# 3xVCO.net
KiCad netlist of a schematic drawn in Altium Designer
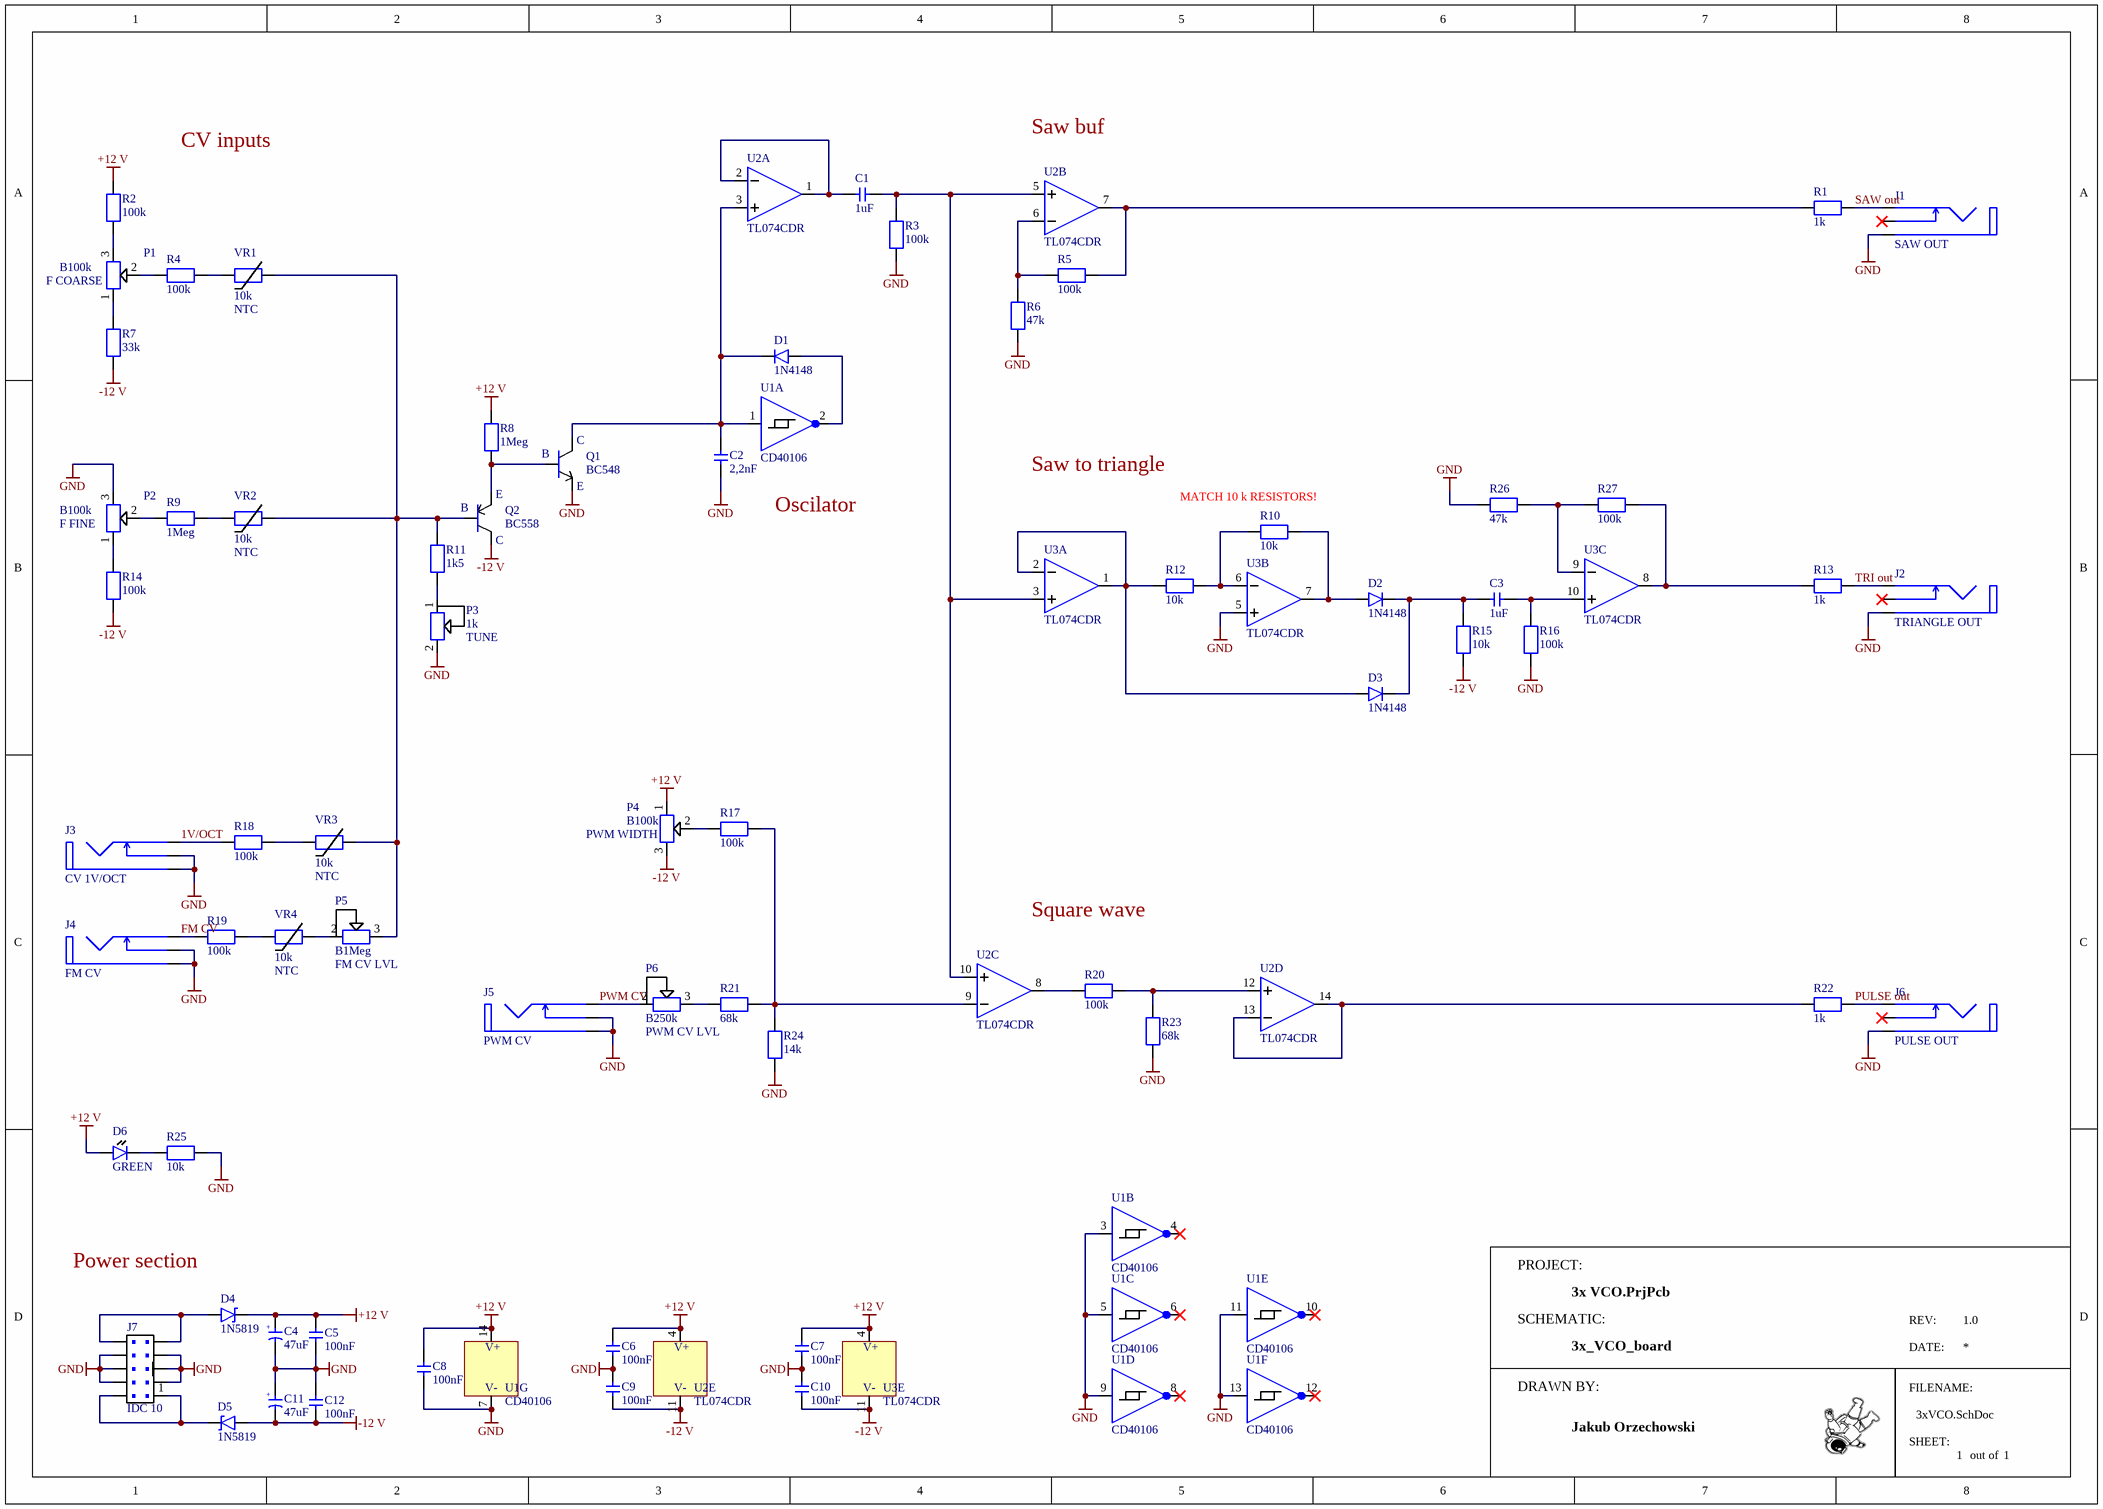
[diagram p0: 3xVCO.SchDoc]

(export (version "E")
  (design (tool "Eeschema 10.0.6"))
  (components
    (comp (ref "C1")
      (value "1uF")
      (footprint "Cap THT 5mm")
      (description "THT Capacitor Non-Polarised 5 mm Pitch")
      (fields (field (name "Comment") "CAP"))
      (libsource (lib "Generic components") (part "Capacitor THT 5mm"))
    )
    (comp (ref "C2")
      (value "2,2nF")
      (footprint "Cap THT 5mm")
      (description "THT Capacitor Non-Polarised 5 mm Pitch")
      (fields (field (name "Comment") "CAP"))
      (libsource (lib "Generic components") (part "Capacitor THT 5mm"))
    )
    (comp (ref "C3")
      (value "1uF")
      (footprint "Cap THT 5mm")
      (description "THT Capacitor Non-Polarised 5 mm Pitch")
      (fields (field (name "Comment") "CAP"))
      (libsource (lib "Generic components") (part "Capacitor THT 5mm"))
    )
    (comp (ref "C4")
      (value "47uF")
      (footprint "Cap electrolytic THT 5mm")
      (description "THT Electrolytic Capacitor 5 mm Diameter")
      (fields (field (name "Comment") "CAP"))
      (libsource (lib "Generic components") (part "Capacitor Electr THT 5mm"))
    )
    (comp (ref "C5")
      (value "100nF")
      (footprint "Cap THT 5mm")
      (description "THT Capacitor Non-Polarised 5 mm Pitch")
      (fields (field (name "Comment") "CAP"))
      (libsource (lib "Generic components") (part "Capacitor THT 5mm"))
    )
    (comp (ref "C6")
      (value "100nF")
      (footprint "Cap THT 5mm")
      (description "THT Capacitor Non-Polarised 5 mm Pitch")
      (fields (field (name "Comment") "CAP"))
      (libsource (lib "Generic components") (part "Capacitor THT 5mm"))
    )
    (comp (ref "C7")
      (value "100nF")
      (footprint "Cap THT 5mm")
      (description "THT Capacitor Non-Polarised 5 mm Pitch")
      (fields (field (name "Comment") "CAP"))
      (libsource (lib "Generic components") (part "Capacitor THT 5mm"))
    )
    (comp (ref "C8")
      (value "100nF")
      (footprint "Cap THT 5mm")
      (description "THT Capacitor Non-Polarised 5 mm Pitch")
      (fields (field (name "Comment") "CAP"))
      (libsource (lib "Generic components") (part "Capacitor THT 5mm"))
    )
    (comp (ref "C9")
      (value "100nF")
      (footprint "Cap THT 5mm")
      (description "THT Capacitor Non-Polarised 5 mm Pitch")
      (fields (field (name "Comment") "CAP"))
      (libsource (lib "Generic components") (part "Capacitor THT 5mm"))
    )
    (comp (ref "C10")
      (value "100nF")
      (footprint "Cap THT 5mm")
      (description "THT Capacitor Non-Polarised 5 mm Pitch")
      (fields (field (name "Comment") "CAP"))
      (libsource (lib "Generic components") (part "Capacitor THT 5mm"))
    )
    (comp (ref "C11")
      (value "47uF")
      (footprint "Cap electrolytic THT 5mm")
      (description "THT Electrolytic Capacitor 5 mm Diameter")
      (fields (field (name "Comment") "CAP"))
      (libsource (lib "Generic components") (part "Capacitor Electr THT 5mm"))
    )
    (comp (ref "C12")
      (value "100nF")
      (footprint "Cap THT 5mm")
      (description "THT Capacitor Non-Polarised 5 mm Pitch")
      (fields (field (name "Comment") "CAP"))
      (libsource (lib "Generic components") (part "Capacitor THT 5mm"))
    )
    (comp (ref "D1")
      (value "DIODE")
      (footprint "Diode THT 10 mm")
      (description "Generic THT Axial Diode 10 mm Pitch")
      (fields (field (name "MODEL") "1N4148"))
      (libsource (lib "Diodes") (part "Diode THT"))
    )
    (comp (ref "D2")
      (value "DIODE")
      (footprint "Diode THT 10 mm")
      (description "Generic THT Axial Diode 10 mm Pitch")
      (fields (field (name "MODEL") "1N4148"))
      (libsource (lib "Diodes") (part "Diode THT"))
    )
    (comp (ref "D3")
      (value "DIODE")
      (footprint "Diode THT 10 mm")
      (description "Generic THT Axial Diode 10 mm Pitch")
      (fields (field (name "MODEL") "1N4148"))
      (libsource (lib "Diodes") (part "Diode THT"))
    )
    (comp (ref "D4")
      (value "SCHOTTKY")
      (footprint "Diode THT 10 mm")
      (description "Generic THT Axial Schottky Diode 10 mm Pitch")
      (fields (field (name "MODEL") "1N5819"))
      (libsource (lib "Diodes") (part "Schottky Diode THT"))
    )
    (comp (ref "D5")
      (value "SCHOTTKY")
      (footprint "Diode THT 10 mm")
      (description "Generic THT Axial Schottky Diode 10 mm Pitch")
      (fields (field (name "MODEL") "1N5819"))
      (libsource (lib "Diodes") (part "Schottky Diode THT"))
    )
    (comp (ref "D6")
      (value "LED")
      (footprint "LED SMD 0805")
      (description "SMD LED Diode 0805 Package")
      (fields (field (name "COLOR") "GREEN"))
      (libsource (lib "Opto") (part "LED SMD"))
    )
    (comp (ref "J1")
      (value "JACK Mono")
      (footprint "PJ301M")
      (description "PJ301M Eurorack 3,5 mm Patch Socket PCB Mount")
      (fields (field (name "LABEL") "SAW OUT"))
      (libsource (lib "Connectors") (part "PJ301M"))
    )
    (comp (ref "J2")
      (value "JACK Mono")
      (footprint "PJ301M")
      (description "PJ301M Eurorack 3,5 mm Patch Socket PCB Mount")
      (fields (field (name "LABEL") "TRIANGLE OUT"))
      (libsource (lib "Connectors") (part "PJ301M"))
    )
    (comp (ref "J3")
      (value "JACK Mono")
      (footprint "PJ301M")
      (description "PJ301M Eurorack 3,5 mm Patch Socket PCB Mount")
      (fields (field (name "LABEL") "CV 1V/OCT"))
      (libsource (lib "Connectors") (part "PJ301M"))
    )
    (comp (ref "J4")
      (value "JACK Mono")
      (footprint "PJ301M")
      (description "PJ301M Eurorack 3,5 mm Patch Socket PCB Mount")
      (fields (field (name "LABEL") "FM CV"))
      (libsource (lib "Connectors") (part "PJ301M"))
    )
    (comp (ref "J5")
      (value "JACK Mono")
      (footprint "PJ301M")
      (description "PJ301M Eurorack 3,5 mm Patch Socket PCB Mount")
      (fields (field (name "LABEL") "PWM CV"))
      (libsource (lib "Connectors") (part "PJ301M"))
    )
    (comp (ref "J6")
      (value "JACK Mono")
      (footprint "PJ301M")
      (description "PJ301M Eurorack 3,5 mm Patch Socket PCB Mount")
      (fields (field (name "LABEL") "PULSE OUT"))
      (libsource (lib "Connectors") (part "PJ301M"))
    )
    (comp (ref "J7")
      (value "IDC 10")
      (footprint "IDC 10 PIN")
      (description "10 Pin IDC Connector")
      (libsource (lib "Connectors") (part "IDC 10 pin"))
    )
    (comp (ref "P1")
      (value "B100k")
      (footprint "Alpha 9mm mono")
      (description "PCB Mount Alpha 9mm Mono Potentiometer THT")
      (fields (field (name "PARAMETER") "F COARSE") (field (name "Comment") "Mono Pot"))
      (libsource (lib "Potentiometers") (part "Potentiometer Alpha 9mm mono"))
    )
    (comp (ref "P2")
      (value "B100k")
      (footprint "9 mm PCB Potentiometer")
      (description "PCB Mount 9mm Mono Potentiometer THT")
      (fields (field (name "PARAMETER") "F FINE") (field (name "Comment") "Mono Pot"))
      (libsource (lib "Potentiometers") (part "Potentiometer 9 mm"))
    )
    (comp (ref "P3")
      (value "1k")
      (footprint "Multiturn Potentiometer inline")
      (description "PCB Mount Multiturn Trimmer Potentiometer Top Adjustable as Variable Resistor Clockwise Increase")
      (fields (field (name "PARAMETER") "TUNE") (field (name "Comment") "VR"))
      (libsource (lib "Potentiometers") (part "VR A Multiturn THT"))
    )
    (comp (ref "P4")
      (value "B100k")
      (footprint "9 mm PCB Potentiometer")
      (description "PCB Mount 9mm Mono Potentiometer THT")
      (fields (field (name "PARAMETER") "PWM WIDTH") (field (name "Comment") "Mono Pot"))
      (libsource (lib "Potentiometers") (part "Potentiometer 9 mm"))
    )
    (comp (ref "P5")
      (value "B1Meg")
      (footprint "9 mm PCB Potentiometer")
      (description "PCB Mount 9mm Mono Potentiometer THT as Variable Resistor Clockwise Decrease")
      (fields (field (name "PARAMETER") "FM CV LVL") (field (name "Comment") "VR"))
      (libsource (lib "Potentiometers") (part "VR B 9 mm"))
    )
    (comp (ref "P6")
      (value "B250k")
      (footprint "9 mm PCB Potentiometer")
      (description "PCB Mount 9mm Mono Potentiometer THT as Variable Resistor Clockwise Decrease")
      (fields (field (name "PARAMETER") "PWM CV LVL") (field (name "Comment") "VR"))
      (libsource (lib "Potentiometers") (part "VR B 9 mm"))
    )
    (comp (ref "Q1")
      (value "BC548")
      (footprint "TO-92 wide")
      (description "BC548 NPN Transistor THT TO-92 Package")
      (libsource (lib "Transistors") (part "BC548"))
    )
    (comp (ref "Q2")
      (value "BC558")
      (footprint "TO-92 wide")
      (description "BC558 PNP Transistor THT TO-92 Package")
      (libsource (lib "Transistors") (part "BC558"))
    )
    (comp (ref "R1")
      (value "1k")
      (footprint "Resistor THT vertical")
      (description "THT Axial Resistor 10mm Pitch")
      (fields (field (name "Comment") "RES"))
      (libsource (lib "Generic components") (part "Resistor THT"))
    )
    (comp (ref "R2")
      (value "100k")
      (footprint "Resistor THT vertical")
      (description "THT Axial Resistor 10mm Pitch")
      (fields (field (name "Comment") "RES"))
      (libsource (lib "Generic components") (part "Resistor THT"))
    )
    (comp (ref "R3")
      (value "100k")
      (footprint "Resistor THT vertical")
      (description "THT Axial Resistor 10mm Pitch")
      (fields (field (name "Comment") "RES"))
      (libsource (lib "Generic components") (part "Resistor THT"))
    )
    (comp (ref "R4")
      (value "100k")
      (footprint "Resistor THT vertical")
      (description "THT Axial Resistor 10mm Pitch")
      (fields (field (name "Comment") "RES"))
      (libsource (lib "Generic components") (part "Resistor THT"))
    )
    (comp (ref "R5")
      (value "100k")
      (footprint "Resistor THT vertical")
      (description "THT Axial Resistor 10mm Pitch")
      (fields (field (name "Comment") "RES"))
      (libsource (lib "Generic components") (part "Resistor THT"))
    )
    (comp (ref "R6")
      (value "47k")
      (footprint "Resistor THT vertical")
      (description "THT Axial Resistor 10mm Pitch")
      (fields (field (name "Comment") "RES"))
      (libsource (lib "Generic components") (part "Resistor THT"))
    )
    (comp (ref "R7")
      (value "33k")
      (footprint "Resistor THT vertical")
      (description "THT Axial Resistor 10mm Pitch")
      (fields (field (name "Comment") "RES"))
      (libsource (lib "Generic components") (part "Resistor THT"))
    )
    (comp (ref "R8")
      (value "1Meg")
      (footprint "Resistor THT vertical")
      (description "THT Axial Resistor 10mm Pitch")
      (fields (field (name "Comment") "RES"))
      (libsource (lib "Generic components") (part "Resistor THT"))
    )
    (comp (ref "R9")
      (value "1Meg")
      (footprint "Resistor THT vertical")
      (description "THT Axial Resistor 10mm Pitch")
      (fields (field (name "Comment") "RES"))
      (libsource (lib "Generic components") (part "Resistor THT"))
    )
    (comp (ref "R10")
      (value "10k")
      (footprint "Resistor THT vertical")
      (description "THT Axial Resistor 10mm Pitch")
      (fields (field (name "Comment") "RES"))
      (libsource (lib "Generic components") (part "Resistor THT"))
    )
    (comp (ref "R11")
      (value "1k5")
      (footprint "Resistor THT vertical")
      (description "THT Axial Resistor 10mm Pitch")
      (fields (field (name "Comment") "RES"))
      (libsource (lib "Generic components") (part "Resistor THT"))
    )
    (comp (ref "R12")
      (value "10k")
      (footprint "Resistor THT vertical")
      (description "THT Axial Resistor 10mm Pitch")
      (fields (field (name "Comment") "RES"))
      (libsource (lib "Generic components") (part "Resistor THT"))
    )
    (comp (ref "R13")
      (value "1k")
      (footprint "Resistor THT vertical")
      (description "THT Axial Resistor 10mm Pitch")
      (fields (field (name "Comment") "RES"))
      (libsource (lib "Generic components") (part "Resistor THT"))
    )
    (comp (ref "R14")
      (value "100k")
      (footprint "Resistor THT vertical")
      (description "THT Axial Resistor 10mm Pitch")
      (fields (field (name "Comment") "RES"))
      (libsource (lib "Generic components") (part "Resistor THT"))
    )
    (comp (ref "R15")
      (value "10k")
      (footprint "Resistor THT vertical")
      (description "THT Axial Resistor 10mm Pitch")
      (fields (field (name "Comment") "RES"))
      (libsource (lib "Generic components") (part "Resistor THT"))
    )
    (comp (ref "R16")
      (value "100k")
      (footprint "Resistor THT vertical")
      (description "THT Axial Resistor 10mm Pitch")
      (fields (field (name "Comment") "RES"))
      (libsource (lib "Generic components") (part "Resistor THT"))
    )
    (comp (ref "R17")
      (value "100k")
      (footprint "Resistor THT vertical")
      (description "THT Axial Resistor 10mm Pitch")
      (fields (field (name "Comment") "RES"))
      (libsource (lib "Generic components") (part "Resistor THT"))
    )
    (comp (ref "R18")
      (value "100k")
      (footprint "Resistor THT vertical")
      (description "THT Axial Resistor 10mm Pitch")
      (fields (field (name "Comment") "RES"))
      (libsource (lib "Generic components") (part "Resistor THT"))
    )
    (comp (ref "R19")
      (value "100k")
      (footprint "Resistor THT vertical")
      (description "THT Axial Resistor 10mm Pitch")
      (fields (field (name "Comment") "RES"))
      (libsource (lib "Generic components") (part "Resistor THT"))
    )
    (comp (ref "R20")
      (value "100k")
      (footprint "Resistor THT vertical")
      (description "THT Axial Resistor 10mm Pitch")
      (fields (field (name "Comment") "RES"))
      (libsource (lib "Generic components") (part "Resistor THT"))
    )
    (comp (ref "R21")
      (value "68k")
      (footprint "Resistor THT vertical")
      (description "THT Axial Resistor 10mm Pitch")
      (fields (field (name "Comment") "RES"))
      (libsource (lib "Generic components") (part "Resistor THT"))
    )
    (comp (ref "R22")
      (value "1k")
      (footprint "Resistor THT vertical")
      (description "THT Axial Resistor 10mm Pitch")
      (fields (field (name "Comment") "RES"))
      (libsource (lib "Generic components") (part "Resistor THT"))
    )
    (comp (ref "R23")
      (value "68k")
      (footprint "Resistor THT vertical")
      (description "THT Axial Resistor 10mm Pitch")
      (fields (field (name "Comment") "RES"))
      (libsource (lib "Generic components") (part "Resistor THT"))
    )
    (comp (ref "R24")
      (value "14k")
      (footprint "Resistor THT vertical")
      (description "THT Axial Resistor 10mm Pitch")
      (fields (field (name "Comment") "RES"))
      (libsource (lib "Generic components") (part "Resistor THT"))
    )
    (comp (ref "R25")
      (value "10k")
      (footprint "Resistor SMD 0805")
      (description "SMD Resistor 0805 package")
      (fields (field (name "Comment") "RES"))
      (libsource (lib "Generic components") (part "Resistor SMD 0805"))
    )
    (comp (ref "R26")
      (value "47k")
      (footprint "Resistor THT vertical")
      (description "THT Axial Resistor 10mm Pitch")
      (fields (field (name "Comment") "RES"))
      (libsource (lib "Generic components") (part "Resistor THT"))
    )
    (comp (ref "R27")
      (value "100k")
      (footprint "Resistor THT vertical")
      (description "THT Axial Resistor 10mm Pitch")
      (fields (field (name "Comment") "RES"))
      (libsource (lib "Generic components") (part "Resistor THT"))
    )
    (comp (ref "U1")
      (value "CD40106")
      (footprint "DIP-14 socket")
      (description "CD40106 Hex Schmitt Trigger Inverter DIP-14 Package")
      (libsource (lib "ICs") (part "CD40106 DIP-14"))
    )
    (comp (ref "U2")
      (value "TL074CDR")
      (footprint "SOIC14")
      (description "TL074CDR Quad Op-Amp SOIC14 Package")
      (libsource (lib "") (part "TL074CDR SOIC14_1"))
    )
    (comp (ref "U3")
      (value "TL074CDR")
      (footprint "SOIC14")
      (description "TL074CDR Quad Op-Amp SOIC14 Package")
      (libsource (lib "OpAmps") (part "TL074CDR SOIC14"))
    )
    (comp (ref "VR1")
      (value "NTC")
      (footprint "THERMISTOR THT 2,54 MM")
      (description "THT NTC Thermistor 2,54 mm Pitch")
      (fields (field (name "ALTIUM_VALUE") "10k"))
      (libsource (lib "Generic components") (part "Thermistor NTC THT"))
    )
    (comp (ref "VR2")
      (value "NTC")
      (footprint "THERMISTOR THT 2,54 MM")
      (description "THT NTC Thermistor 2,54 mm Pitch")
      (fields (field (name "ALTIUM_VALUE") "10k"))
      (libsource (lib "Generic components") (part "Thermistor NTC THT"))
    )
    (comp (ref "VR3")
      (value "NTC")
      (footprint "THERMISTOR THT 2,54 MM")
      (description "THT NTC Thermistor 2,54 mm Pitch")
      (fields (field (name "ALTIUM_VALUE") "10k"))
      (libsource (lib "Generic components") (part "Thermistor NTC THT"))
    )
    (comp (ref "VR4")
      (value "NTC")
      (footprint "THERMISTOR THT 2,54 MM")
      (description "THT NTC Thermistor 2,54 mm Pitch")
      (fields (field (name "ALTIUM_VALUE") "10k"))
      (libsource (lib "Generic components") (part "Thermistor NTC THT"))
    )
  )
  (nets
    (net (code "1") (name "+12 V") (class "Default")
      (node (ref "C4") (pin "2") (pintype "passive"))
      (node (ref "C5") (pin "2") (pintype "passive"))
      (node (ref "C6") (pin "2") (pintype "passive"))
      (node (ref "C7") (pin "2") (pintype "passive"))
      (node (ref "C8") (pin "2") (pintype "passive"))
      (node (ref "D4") (pin "2") (pintype "passive"))
      (node (ref "D6") (pin "1") (pintype "passive"))
      (node (ref "P4") (pin "1") (pintype "passive"))
      (node (ref "R2") (pin "2") (pintype "passive"))
      (node (ref "R8") (pin "1") (pintype "passive"))
      (node (ref "U1") (pin "14") (pintype "passive"))
      (node (ref "U2") (pin "4") (pintype "passive"))
      (node (ref "U3") (pin "4") (pintype "passive"))
    )
    (net (code "2") (name "-12 V") (class "Default")
      (node (ref "C10") (pin "1") (pintype "passive"))
      (node (ref "C11") (pin "1") (pintype "passive"))
      (node (ref "C12") (pin "1") (pintype "passive"))
      (node (ref "C9") (pin "1") (pintype "passive"))
      (node (ref "D5") (pin "1") (pintype "passive"))
      (node (ref "P4") (pin "3") (pintype "passive"))
      (node (ref "Q2") (pin "1") (pintype "passive"))
      (node (ref "R14") (pin "1") (pintype "passive"))
      (node (ref "R15") (pin "2") (pintype "passive"))
      (node (ref "R7") (pin "1") (pintype "passive"))
      (node (ref "U2") (pin "11") (pintype "passive"))
      (node (ref "U3") (pin "11") (pintype "passive"))
    )
    (net (code "3") (name "/1V{slash}OCT") (class "Default")
      (node (ref "J3") (pin "3") (pintype "passive"))
      (node (ref "R18") (pin "2") (pintype "passive"))
    )
    (net (code "4") (name "/FM CV") (class "Default")
      (node (ref "J4") (pin "3") (pintype "passive"))
      (node (ref "R19") (pin "2") (pintype "passive"))
    )
    (net (code "5") (name "/PULSE out") (class "Default")
      (node (ref "J6") (pin "3") (pintype "passive"))
      (node (ref "R22") (pin "2") (pintype "passive"))
    )
    (net (code "6") (name "/PWM CV") (class "Default")
      (node (ref "J5") (pin "3") (pintype "passive"))
      (node (ref "P6") (pin "2") (pintype "passive"))
    )
    (net (code "7") (name "/SAW out") (class "Default")
      (node (ref "J1") (pin "3") (pintype "passive"))
      (node (ref "R1") (pin "2") (pintype "passive"))
    )
    (net (code "8") (name "/TRI out") (class "Default")
      (node (ref "J2") (pin "3") (pintype "passive"))
      (node (ref "R13") (pin "2") (pintype "passive"))
    )
    (net (code "9") (name "GND") (class "Default")
      (node (ref "C10") (pin "2") (pintype "passive"))
      (node (ref "C11") (pin "2") (pintype "passive"))
      (node (ref "C12") (pin "2") (pintype "passive"))
      (node (ref "C2") (pin "1") (pintype "passive"))
      (node (ref "C4") (pin "1") (pintype "passive"))
      (node (ref "C5") (pin "1") (pintype "passive"))
      (node (ref "C6") (pin "1") (pintype "passive"))
      (node (ref "C7") (pin "1") (pintype "passive"))
      (node (ref "C8") (pin "1") (pintype "passive"))
      (node (ref "C9") (pin "2") (pintype "passive"))
      (node (ref "J1") (pin "1") (pintype "passive"))
      (node (ref "J2") (pin "1") (pintype "passive"))
      (node (ref "J3") (pin "1") (pintype "passive"))
      (node (ref "J3") (pin "2") (pintype "passive"))
      (node (ref "J4") (pin "1") (pintype "passive"))
      (node (ref "J4") (pin "2") (pintype "passive"))
      (node (ref "J5") (pin "1") (pintype "passive"))
      (node (ref "J5") (pin "2") (pintype "passive"))
      (node (ref "J6") (pin "1") (pintype "passive"))
      (node (ref "J7") (pin "3") (pintype "passive"))
      (node (ref "J7") (pin "4") (pintype "passive"))
      (node (ref "J7") (pin "5") (pintype "passive"))
      (node (ref "J7") (pin "6") (pintype "passive"))
      (node (ref "J7") (pin "7") (pintype "passive"))
      (node (ref "J7") (pin "8") (pintype "passive"))
      (node (ref "P2") (pin "3") (pintype "passive"))
      (node (ref "P3") (pin "2") (pintype "passive"))
      (node (ref "Q1") (pin "3") (pintype "passive"))
      (node (ref "R16") (pin "2") (pintype "passive"))
      (node (ref "R23") (pin "1") (pintype "passive"))
      (node (ref "R24") (pin "1") (pintype "passive"))
      (node (ref "R25") (pin "2") (pintype "passive"))
      (node (ref "R26") (pin "1") (pintype "passive"))
      (node (ref "R3") (pin "2") (pintype "passive"))
      (node (ref "R6") (pin "2") (pintype "passive"))
      (node (ref "U1") (pin "11") (pintype "passive"))
      (node (ref "U1") (pin "13") (pintype "passive"))
      (node (ref "U1") (pin "3") (pintype "passive"))
      (node (ref "U1") (pin "5") (pintype "passive"))
      (node (ref "U1") (pin "7") (pintype "passive"))
      (node (ref "U1") (pin "9") (pintype "passive"))
      (node (ref "U3") (pin "5") (pintype "passive"))
    )
    (net (code "10") (name "Net-(C1-Pad1)") (class "Default")
      (node (ref "C1") (pin "1") (pintype "passive"))
      (node (ref "R3") (pin "1") (pintype "passive"))
      (node (ref "U2") (pin "10") (pintype "passive"))
      (node (ref "U2") (pin "5") (pintype "passive"))
      (node (ref "U3") (pin "3") (pintype "passive"))
    )
    (net (code "11") (name "Net-(C1-Pad2)") (class "Default")
      (node (ref "C1") (pin "2") (pintype "passive"))
      (node (ref "U2") (pin "1") (pintype "passive"))
      (node (ref "U2") (pin "2") (pintype "passive"))
    )
    (net (code "12") (name "Net-(C2-Pad2)") (class "Default")
      (node (ref "C2") (pin "2") (pintype "passive"))
      (node (ref "D1") (pin "2") (pintype "passive"))
      (node (ref "Q1") (pin "1") (pintype "passive"))
      (node (ref "U1") (pin "1") (pintype "passive"))
      (node (ref "U2") (pin "3") (pintype "passive"))
    )
    (net (code "13") (name "Net-(C3-Pad1)") (class "Default")
      (node (ref "C3") (pin "1") (pintype "passive"))
      (node (ref "R16") (pin "1") (pintype "passive"))
      (node (ref "U3") (pin "10") (pintype "passive"))
    )
    (net (code "14") (name "Net-(C3-Pad2)") (class "Default")
      (node (ref "C3") (pin "2") (pintype "passive"))
      (node (ref "D2") (pin "2") (pintype "passive"))
      (node (ref "D3") (pin "2") (pintype "passive"))
      (node (ref "R15") (pin "1") (pintype "passive"))
    )
    (net (code "15") (name "Net-(D1-Pad1)") (class "Default")
      (node (ref "D1") (pin "1") (pintype "passive"))
      (node (ref "U1") (pin "2") (pintype "passive"))
    )
    (net (code "16") (name "Net-(D2-Pad1)") (class "Default")
      (node (ref "D2") (pin "1") (pintype "passive"))
      (node (ref "R10") (pin "2") (pintype "passive"))
      (node (ref "U3") (pin "7") (pintype "passive"))
    )
    (net (code "17") (name "Net-(D3-Pad1)") (class "Default")
      (node (ref "D3") (pin "1") (pintype "passive"))
      (node (ref "R12") (pin "1") (pintype "passive"))
      (node (ref "U3") (pin "1") (pintype "passive"))
      (node (ref "U3") (pin "2") (pintype "passive"))
    )
    (net (code "18") (name "Net-(D4-Pad1)") (class "Default")
      (node (ref "D4") (pin "1") (pintype "passive"))
      (node (ref "J7") (pin "10") (pintype "passive"))
      (node (ref "J7") (pin "9") (pintype "passive"))
    )
    (net (code "19") (name "Net-(D5-Pad2)") (class "Default")
      (node (ref "D5") (pin "2") (pintype "passive"))
      (node (ref "J7") (pin "1") (pintype "passive"))
      (node (ref "J7") (pin "2") (pintype "passive"))
    )
    (net (code "20") (name "Net-(D6-Pad2)") (class "Default")
      (node (ref "D6") (pin "2") (pintype "passive"))
      (node (ref "R25") (pin "1") (pintype "passive"))
    )
    (net (code "21") (name "Net-(P1-Pad1)") (class "Default")
      (node (ref "P1") (pin "1") (pintype "passive"))
      (node (ref "R7") (pin "2") (pintype "passive"))
    )
    (net (code "22") (name "Net-(P1-Pad2)") (class "Default")
      (node (ref "P1") (pin "2") (pintype "passive"))
      (node (ref "R4") (pin "2") (pintype "passive"))
    )
    (net (code "23") (name "Net-(P1-Pad3)") (class "Default")
      (node (ref "P1") (pin "3") (pintype "passive"))
      (node (ref "R2") (pin "1") (pintype "passive"))
    )
    (net (code "24") (name "Net-(P2-Pad1)") (class "Default")
      (node (ref "P2") (pin "1") (pintype "passive"))
      (node (ref "R14") (pin "2") (pintype "passive"))
    )
    (net (code "25") (name "Net-(P2-Pad2)") (class "Default")
      (node (ref "P2") (pin "2") (pintype "passive"))
      (node (ref "R9") (pin "2") (pintype "passive"))
    )
    (net (code "26") (name "Net-(P3-Pad1)") (class "Default")
      (node (ref "P3") (pin "1") (pintype "passive"))
      (node (ref "R11") (pin "2") (pintype "passive"))
    )
    (net (code "27") (name "Net-(P4-Pad2)") (class "Default")
      (node (ref "P4") (pin "2") (pintype "passive"))
      (node (ref "R17") (pin "1") (pintype "passive"))
    )
    (net (code "28") (name "Net-(P5-Pad2)") (class "Default")
      (node (ref "P5") (pin "2") (pintype "passive"))
      (node (ref "VR4") (pin "2") (pintype "passive"))
    )
    (net (code "29") (name "Net-(P5-Pad3)") (class "Default")
      (node (ref "P5") (pin "3") (pintype "passive"))
      (node (ref "Q2") (pin "2") (pintype "passive"))
      (node (ref "R11") (pin "1") (pintype "passive"))
      (node (ref "VR1") (pin "2") (pintype "passive"))
      (node (ref "VR2") (pin "2") (pintype "passive"))
      (node (ref "VR3") (pin "2") (pintype "passive"))
    )
    (net (code "30") (name "Net-(P6-Pad3)") (class "Default")
      (node (ref "P6") (pin "3") (pintype "passive"))
      (node (ref "R21") (pin "1") (pintype "passive"))
    )
    (net (code "31") (name "Net-(Q1-Pad2)") (class "Default")
      (node (ref "Q1") (pin "2") (pintype "passive"))
      (node (ref "Q2") (pin "3") (pintype "passive"))
      (node (ref "R8") (pin "2") (pintype "passive"))
    )
    (net (code "32") (name "Net-(R1-Pad1)") (class "Default")
      (node (ref "R1") (pin "1") (pintype "passive"))
      (node (ref "R5") (pin "2") (pintype "passive"))
      (node (ref "U2") (pin "7") (pintype "passive"))
    )
    (net (code "33") (name "Net-(R4-Pad1)") (class "Default")
      (node (ref "R4") (pin "1") (pintype "passive"))
      (node (ref "VR1") (pin "1") (pintype "passive"))
    )
    (net (code "34") (name "Net-(R5-Pad1)") (class "Default")
      (node (ref "R5") (pin "1") (pintype "passive"))
      (node (ref "R6") (pin "1") (pintype "passive"))
      (node (ref "U2") (pin "6") (pintype "passive"))
    )
    (net (code "35") (name "Net-(R9-Pad1)") (class "Default")
      (node (ref "R9") (pin "1") (pintype "passive"))
      (node (ref "VR2") (pin "1") (pintype "passive"))
    )
    (net (code "36") (name "Net-(R10-Pad1)") (class "Default")
      (node (ref "R10") (pin "1") (pintype "passive"))
      (node (ref "R12") (pin "2") (pintype "passive"))
      (node (ref "U3") (pin "6") (pintype "passive"))
    )
    (net (code "37") (name "Net-(R13-Pad1)") (class "Default")
      (node (ref "R13") (pin "1") (pintype "passive"))
      (node (ref "R27") (pin "2") (pintype "passive"))
      (node (ref "U3") (pin "8") (pintype "passive"))
    )
    (net (code "38") (name "Net-(R17-Pad2)") (class "Default")
      (node (ref "R17") (pin "2") (pintype "passive"))
      (node (ref "R21") (pin "2") (pintype "passive"))
      (node (ref "R24") (pin "2") (pintype "passive"))
      (node (ref "U2") (pin "9") (pintype "passive"))
    )
    (net (code "39") (name "Net-(R18-Pad1)") (class "Default")
      (node (ref "R18") (pin "1") (pintype "passive"))
      (node (ref "VR3") (pin "1") (pintype "passive"))
    )
    (net (code "40") (name "Net-(R19-Pad1)") (class "Default")
      (node (ref "R19") (pin "1") (pintype "passive"))
      (node (ref "VR4") (pin "1") (pintype "passive"))
    )
    (net (code "41") (name "Net-(R20-Pad1)") (class "Default")
      (node (ref "R20") (pin "1") (pintype "passive"))
      (node (ref "U2") (pin "8") (pintype "passive"))
    )
    (net (code "42") (name "Net-(R20-Pad2)") (class "Default")
      (node (ref "R20") (pin "2") (pintype "passive"))
      (node (ref "R23") (pin "2") (pintype "passive"))
      (node (ref "U2") (pin "12") (pintype "passive"))
    )
    (net (code "43") (name "Net-(R22-Pad1)") (class "Default")
      (node (ref "R22") (pin "1") (pintype "passive"))
      (node (ref "U2") (pin "13") (pintype "passive"))
      (node (ref "U2") (pin "14") (pintype "passive"))
    )
    (net (code "44") (name "Net-(R26-Pad2)") (class "Default")
      (node (ref "R26") (pin "2") (pintype "passive"))
      (node (ref "R27") (pin "1") (pintype "passive"))
      (node (ref "U3") (pin "9") (pintype "passive"))
    )
    (net (code "45") (name "unconnected-(J1-Pad2)") (class "Default")
      (node (ref "J1") (pin "2") (pintype "passive+no_connect"))
    )
    (net (code "46") (name "unconnected-(J2-Pad2)") (class "Default")
      (node (ref "J2") (pin "2") (pintype "passive+no_connect"))
    )
    (net (code "47") (name "unconnected-(J6-Pad2)") (class "Default")
      (node (ref "J6") (pin "2") (pintype "passive+no_connect"))
    )
    (net (code "48") (name "unconnected-(U1-Pad4)") (class "Default")
      (node (ref "U1") (pin "4") (pintype "passive+no_connect"))
    )
    (net (code "49") (name "unconnected-(U1-Pad6)") (class "Default")
      (node (ref "U1") (pin "6") (pintype "passive+no_connect"))
    )
    (net (code "50") (name "unconnected-(U1-Pad8)") (class "Default")
      (node (ref "U1") (pin "8") (pintype "passive+no_connect"))
    )
    (net (code "51") (name "unconnected-(U1-Pad10)") (class "Default")
      (node (ref "U1") (pin "10") (pintype "passive+no_connect"))
    )
    (net (code "52") (name "unconnected-(U1-Pad12)") (class "Default")
      (node (ref "U1") (pin "12") (pintype "passive+no_connect"))
    )
  )
)
